# PART_2.net
KiCad netlist of a schematic drawn in Altium Designer
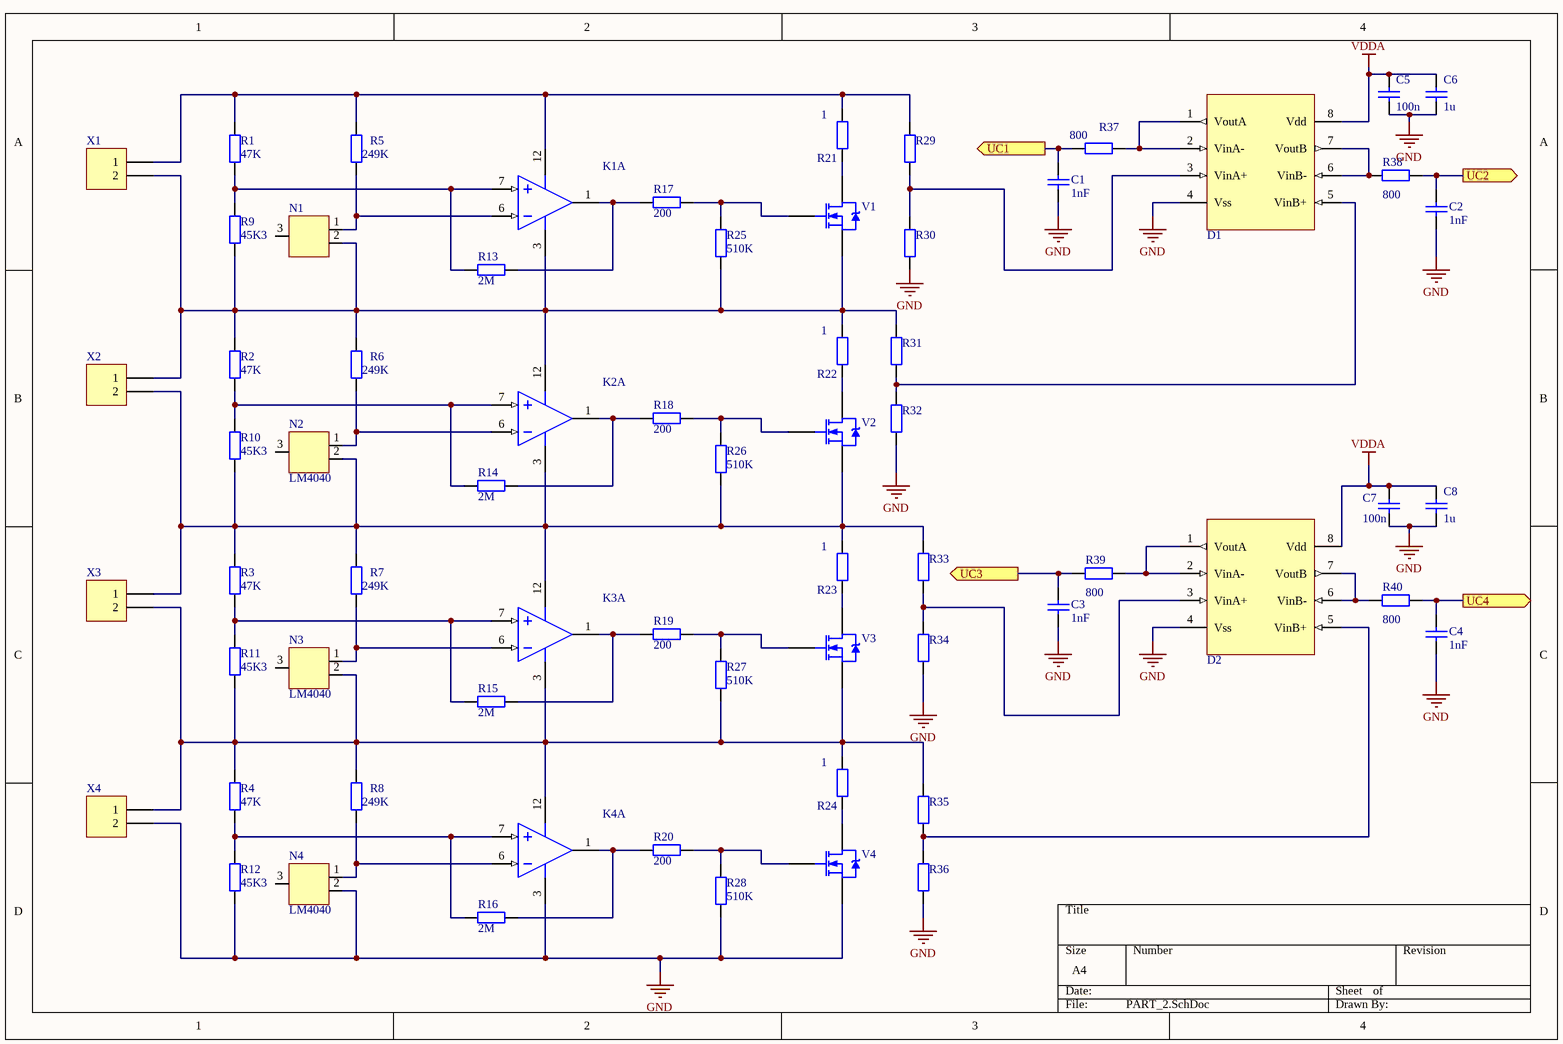
[diagram p0: PART_2.SchDoc]

(export (version "E")
  (design (tool "Eeschema 10.0.6"))
  (components
    (comp (ref "C1")
      (value "1nF")
      (footprint "C0805")
      (description "Capacitor")
      (fields (field (name "Comment") "Cap"))
      (libsource (lib "Miscellaneous Devices") (part "Cap"))
    )
    (comp (ref "C2")
      (value "1nF")
      (footprint "C0805")
      (description "Capacitor")
      (fields (field (name "Comment") "Cap"))
      (libsource (lib "Miscellaneous Devices") (part "Cap"))
    )
    (comp (ref "C3")
      (value "1nF")
      (footprint "C0805")
      (description "Capacitor")
      (fields (field (name "Comment") "Cap"))
      (libsource (lib "Miscellaneous Devices") (part "Cap"))
    )
    (comp (ref "C4")
      (value "1nF")
      (footprint "C0805")
      (description "Capacitor")
      (fields (field (name "Comment") "Cap"))
      (libsource (lib "Miscellaneous Devices") (part "Cap"))
    )
    (comp (ref "C5")
      (value "100n")
      (footprint "C0805")
      (description "Capacitor")
      (libsource (lib "Miscellaneous Devices") (part "Cap"))
    )
    (comp (ref "C6")
      (value "1u")
      (footprint "C0805")
      (description "Capacitor")
      (libsource (lib "Miscellaneous Devices") (part "Cap"))
    )
    (comp (ref "C7")
      (value "100n")
      (footprint "C0805")
      (description "Capacitor")
      (libsource (lib "Miscellaneous Devices") (part "Cap"))
    )
    (comp (ref "C8")
      (value "1u")
      (footprint "C0805")
      (description "Capacitor")
      (libsource (lib "Miscellaneous Devices") (part "Cap"))
    )
    (comp (ref "D1")
      (value "~")
      (footprint "MSOP za MCP6242")
      (libsource (lib "komponente") (part "Amplifier"))
    )
    (comp (ref "D2")
      (value "~")
      (footprint "MSOP za MCP6242")
      (libsource (lib "komponente") (part "Amplifier"))
    )
    (comp (ref "K1")
      (value "TLC3704QJ")
      (footprint "TSSOP5-3")
      (description "Low Power Quad Differential Comparator")
      (libsource (lib "TI Analog Comparator") (part "LP2901D"))
    )
    (comp (ref "K2")
      (value "TLC3704QJ")
      (footprint "TSSOP5-3")
      (description "Low Power Quad Differential Comparator")
      (libsource (lib "TI Analog Comparator") (part "LP2901D"))
    )
    (comp (ref "K3")
      (value "TLC3704QJ")
      (footprint "TSSOP5-3")
      (description "Low Power Quad Differential Comparator")
      (libsource (lib "TI Analog Comparator") (part "LP2901D"))
    )
    (comp (ref "K4")
      (value "TLC3704QJ")
      (footprint "TSSOP5-3")
      (description "Low Power Quad Differential Comparator")
      (libsource (lib "TI Analog Comparator") (part "LP2901D"))
    )
    (comp (ref "N1")
      (value "~")
      (footprint "SOT-23-ref_chip")
      (libsource (lib "komponente") (part "referentni chip"))
    )
    (comp (ref "N2")
      (value "LM4040")
      (footprint "SOT-23-ref_chip")
      (libsource (lib "komponente") (part "referentni chip"))
    )
    (comp (ref "N3")
      (value "LM4040")
      (footprint "SOT-23-ref_chip")
      (libsource (lib "komponente") (part "referentni chip"))
    )
    (comp (ref "N4")
      (value "LM4040")
      (footprint "SOT-23-ref_chip")
      (libsource (lib "komponente") (part "referentni chip"))
    )
    (comp (ref "R1")
      (value "47K")
      (footprint "C0805")
      (description "Resistor")
      (libsource (lib "Miscellaneous Devices") (part "Res2"))
    )
    (comp (ref "R2")
      (value "47K")
      (footprint "C0805")
      (description "Resistor")
      (libsource (lib "Miscellaneous Devices") (part "Res2"))
    )
    (comp (ref "R3")
      (value "47K")
      (footprint "C0805")
      (description "Resistor")
      (libsource (lib "Miscellaneous Devices") (part "Res2"))
    )
    (comp (ref "R4")
      (value "47K")
      (footprint "C0805")
      (description "Resistor")
      (libsource (lib "Miscellaneous Devices") (part "Res2"))
    )
    (comp (ref "R5")
      (value "249K")
      (footprint "C0805")
      (description "Resistor")
      (libsource (lib "Miscellaneous Devices") (part "Res2"))
    )
    (comp (ref "R6")
      (value "249K")
      (footprint "C0805")
      (description "Resistor")
      (libsource (lib "Miscellaneous Devices") (part "Res2"))
    )
    (comp (ref "R7")
      (value "249K")
      (footprint "C0805")
      (description "Resistor")
      (libsource (lib "Miscellaneous Devices") (part "Res2"))
    )
    (comp (ref "R8")
      (value "249K")
      (footprint "C0805")
      (description "Resistor")
      (libsource (lib "Miscellaneous Devices") (part "Res2"))
    )
    (comp (ref "R9")
      (value "45K3")
      (footprint "C0805")
      (description "Resistor")
      (libsource (lib "Miscellaneous Devices") (part "Res2"))
    )
    (comp (ref "R10")
      (value "45K3")
      (footprint "C0805")
      (description "Resistor")
      (libsource (lib "Miscellaneous Devices") (part "Res2"))
    )
    (comp (ref "R11")
      (value "45K3")
      (footprint "C0805")
      (description "Resistor")
      (libsource (lib "Miscellaneous Devices") (part "Res2"))
    )
    (comp (ref "R12")
      (value "45K3")
      (footprint "C0805")
      (description "Resistor")
      (libsource (lib "Miscellaneous Devices") (part "Res2"))
    )
    (comp (ref "R13")
      (value "2M")
      (footprint "C0805")
      (description "Resistor")
      (libsource (lib "") (part "Res2_1"))
    )
    (comp (ref "R14")
      (value "2M")
      (footprint "C0805")
      (description "Resistor")
      (libsource (lib "") (part "Res2_1"))
    )
    (comp (ref "R15")
      (value "2M")
      (footprint "C0805")
      (description "Resistor")
      (libsource (lib "") (part "Res2_1"))
    )
    (comp (ref "R16")
      (value "2M")
      (footprint "C0805")
      (description "Resistor")
      (libsource (lib "") (part "Res2_1"))
    )
    (comp (ref "R17")
      (value "200")
      (footprint "C0805")
      (description "Resistor")
      (libsource (lib "") (part "Res2_1"))
    )
    (comp (ref "R18")
      (value "200")
      (footprint "C0805")
      (description "Resistor")
      (libsource (lib "") (part "Res2_1"))
    )
    (comp (ref "R19")
      (value "200")
      (footprint "C0805")
      (description "Resistor")
      (libsource (lib "") (part "Res2_1"))
    )
    (comp (ref "R20")
      (value "200")
      (footprint "C0805")
      (description "Resistor")
      (libsource (lib "") (part "Res2_1"))
    )
    (comp (ref "R21")
      (value "1")
      (footprint "F za 7W otpornik")
      (description "Resistor")
      (libsource (lib "Miscellaneous Devices") (part "Res2"))
    )
    (comp (ref "R22")
      (value "1")
      (footprint "F za 7W otpornik")
      (description "Resistor")
      (libsource (lib "Miscellaneous Devices") (part "Res2"))
    )
    (comp (ref "R23")
      (value "1")
      (footprint "F za 7W otpornik")
      (description "Resistor")
      (libsource (lib "Miscellaneous Devices") (part "Res2"))
    )
    (comp (ref "R24")
      (value "1")
      (footprint "F za 7W otpornik")
      (description "Resistor")
      (libsource (lib "Miscellaneous Devices") (part "Res2"))
    )
    (comp (ref "R25")
      (value "510K")
      (footprint "C0805")
      (description "Resistor")
      (libsource (lib "Miscellaneous Devices") (part "Res2"))
    )
    (comp (ref "R26")
      (value "510K")
      (footprint "C0805")
      (description "Resistor")
      (libsource (lib "Miscellaneous Devices") (part "Res2"))
    )
    (comp (ref "R27")
      (value "510K")
      (footprint "C0805")
      (description "Resistor")
      (libsource (lib "Miscellaneous Devices") (part "Res2"))
    )
    (comp (ref "R28")
      (value "510K")
      (footprint "C0805")
      (description "Resistor")
      (libsource (lib "Miscellaneous Devices") (part "Res2"))
    )
    (comp (ref "R29")
      (value "~")
      (footprint "C0805")
      (description "Resistor")
      (libsource (lib "Miscellaneous Devices") (part "Res2"))
    )
    (comp (ref "R30")
      (value "~")
      (footprint "C0805")
      (description "Resistor")
      (libsource (lib "Miscellaneous Devices") (part "Res2"))
    )
    (comp (ref "R31")
      (value "~")
      (footprint "C0805")
      (description "Resistor")
      (libsource (lib "Miscellaneous Devices") (part "Res2"))
    )
    (comp (ref "R32")
      (value "~")
      (footprint "C0805")
      (description "Resistor")
      (libsource (lib "Miscellaneous Devices") (part "Res2"))
    )
    (comp (ref "R33")
      (value "~")
      (footprint "C0805")
      (description "Resistor")
      (libsource (lib "Miscellaneous Devices") (part "Res2"))
    )
    (comp (ref "R34")
      (value "~")
      (footprint "C0805")
      (description "Resistor")
      (libsource (lib "Miscellaneous Devices") (part "Res2"))
    )
    (comp (ref "R35")
      (value "~")
      (footprint "C0805")
      (description "Resistor")
      (libsource (lib "Miscellaneous Devices") (part "Res2"))
    )
    (comp (ref "R36")
      (value "~")
      (footprint "C0805")
      (description "Resistor")
      (libsource (lib "Miscellaneous Devices") (part "Res2"))
    )
    (comp (ref "R37")
      (value "800")
      (footprint "C0805")
      (description "Resistor")
      (libsource (lib "") (part "Res2_1"))
    )
    (comp (ref "R38")
      (value "800")
      (footprint "C0805")
      (description "Resistor")
      (libsource (lib "") (part "Res2_2"))
    )
    (comp (ref "R39")
      (value "800")
      (footprint "C0805")
      (description "Resistor")
      (libsource (lib "") (part "Res2_2"))
    )
    (comp (ref "R40")
      (value "800")
      (footprint "C0805")
      (description "Resistor")
      (libsource (lib "") (part "Res2_2"))
    )
    (comp (ref "V1")
      (value "NMOS-2")
      (footprint "SO-8L single_f")
      (description "N-Channel Power MOSFET")
      (libsource (lib "Miscellaneous Devices") (part "NMOS-2"))
    )
    (comp (ref "V2")
      (value "NMOS-2")
      (footprint "SO-8L single_f")
      (description "N-Channel Power MOSFET")
      (libsource (lib "Miscellaneous Devices") (part "NMOS-2"))
    )
    (comp (ref "V3")
      (value "NMOS-2")
      (footprint "SO-8L single_f")
      (description "N-Channel Power MOSFET")
      (libsource (lib "Miscellaneous Devices") (part "NMOS-2"))
    )
    (comp (ref "V4")
      (value "NMOS-2")
      (footprint "SO-8L single_f")
      (description "N-Channel Power MOSFET")
      (libsource (lib "Miscellaneous Devices") (part "NMOS-2"))
    )
    (comp (ref "X1")
      (value "Header 2")
      (footprint "F Header 1x2")
      (description "Header, 2-Pin")
      (libsource (lib "Miscellaneous Connectors") (part "Header 2"))
    )
    (comp (ref "X2")
      (value "Header 2")
      (footprint "F Header 1x2")
      (description "Header, 2-Pin")
      (libsource (lib "Miscellaneous Connectors") (part "Header 2"))
    )
    (comp (ref "X3")
      (value "Header 2")
      (footprint "F Header 1x2")
      (description "Header, 2-Pin")
      (libsource (lib "Miscellaneous Connectors") (part "Header 2"))
    )
    (comp (ref "X4")
      (value "Header 2")
      (footprint "F Header 1x2")
      (description "Header, 2-Pin")
      (libsource (lib "Miscellaneous Connectors") (part "Header 2"))
    )
  )
  (nets
    (net (code "1") (name "/UC1") (class "Default")
      (node (ref "C1") (pin "2") (pinfunction "2_2") (pintype "passive"))
      (node (ref "R37") (pin "2") (pinfunction "2_2") (pintype "passive"))
    )
    (net (code "2") (name "/UC2") (class "Default")
      (node (ref "C2") (pin "2") (pinfunction "2_2") (pintype "passive"))
      (node (ref "R38") (pin "2") (pinfunction "2_2") (pintype "passive"))
    )
    (net (code "3") (name "/UC3") (class "Default")
      (node (ref "C3") (pin "2") (pinfunction "2_2") (pintype "passive"))
      (node (ref "R39") (pin "1") (pinfunction "1_1") (pintype "passive"))
    )
    (net (code "4") (name "/UC4") (class "Default")
      (node (ref "C4") (pin "2") (pinfunction "2_2") (pintype "passive"))
      (node (ref "R40") (pin "2") (pinfunction "2_2") (pintype "passive"))
    )
    (net (code "5") (name "GND") (class "Default")
      (node (ref "C1") (pin "1") (pinfunction "1_1") (pintype "passive"))
      (node (ref "C2") (pin "1") (pinfunction "1_1") (pintype "passive"))
      (node (ref "C3") (pin "1") (pinfunction "1_1") (pintype "passive"))
      (node (ref "C4") (pin "1") (pinfunction "1_1") (pintype "passive"))
      (node (ref "C5") (pin "2") (pinfunction "2_2") (pintype "passive"))
      (node (ref "C6") (pin "2") (pinfunction "2_2") (pintype "passive"))
      (node (ref "C7") (pin "2") (pinfunction "2_2") (pintype "passive"))
      (node (ref "C8") (pin "2") (pinfunction "2_2") (pintype "passive"))
      (node (ref "D1") (pin "4") (pinfunction "Vss_4") (pintype "power_in"))
      (node (ref "D2") (pin "4") (pinfunction "Vss_4") (pintype "power_in"))
      (node (ref "K4") (pin "3") (pinfunction "V+_3") (pintype "passive"))
      (node (ref "N4") (pin "2") (pinfunction "2_2") (pintype "passive"))
      (node (ref "R12") (pin "1") (pinfunction "1_1") (pintype "passive"))
      (node (ref "R28") (pin "1") (pinfunction "1_1") (pintype "passive"))
      (node (ref "R30") (pin "1") (pinfunction "1_1") (pintype "passive"))
      (node (ref "R32") (pin "1") (pinfunction "1_1") (pintype "passive"))
      (node (ref "R34") (pin "1") (pinfunction "1_1") (pintype "passive"))
      (node (ref "R36") (pin "1") (pinfunction "1_1") (pintype "passive"))
      (node (ref "V4") (pin "3") (pinfunction "S_3") (pintype "passive"))
      (node (ref "X4") (pin "2") (pinfunction "2_2") (pintype "passive"))
    )
    (net (code "6") (name "Net-(D1-VinA+)") (class "Default")
      (node (ref "D1") (pin "3") (pinfunction "VinA+_3") (pintype "input"))
      (node (ref "R29") (pin "1") (pinfunction "1_1") (pintype "passive"))
      (node (ref "R30") (pin "2") (pinfunction "2_2") (pintype "passive"))
    )
    (net (code "7") (name "Net-(D1-VinA-)") (class "Default")
      (node (ref "D1") (pin "1") (pinfunction "VoutA_1") (pintype "output"))
      (node (ref "D1") (pin "2") (pinfunction "VinA-_2") (pintype "input"))
      (node (ref "R37") (pin "1") (pinfunction "1_1") (pintype "passive"))
    )
    (net (code "8") (name "Net-(D1-VinB+)") (class "Default")
      (node (ref "D1") (pin "5") (pinfunction "VinB+_5") (pintype "input"))
      (node (ref "R31") (pin "1") (pinfunction "1_1") (pintype "passive"))
      (node (ref "R32") (pin "2") (pinfunction "2_2") (pintype "passive"))
    )
    (net (code "9") (name "Net-(D1-VinB-)") (class "Default")
      (node (ref "D1") (pin "6") (pinfunction "VinB-_6") (pintype "input"))
      (node (ref "D1") (pin "7") (pinfunction "VoutB_7") (pintype "output"))
      (node (ref "R38") (pin "1") (pinfunction "1_1") (pintype "passive"))
    )
    (net (code "10") (name "Net-(D2-VinA+)") (class "Default")
      (node (ref "D2") (pin "3") (pinfunction "VinA+_3") (pintype "input"))
      (node (ref "R33") (pin "1") (pinfunction "1_1") (pintype "passive"))
      (node (ref "R34") (pin "2") (pinfunction "2_2") (pintype "passive"))
    )
    (net (code "11") (name "Net-(D2-VinA-)") (class "Default")
      (node (ref "D2") (pin "1") (pinfunction "VoutA_1") (pintype "output"))
      (node (ref "D2") (pin "2") (pinfunction "VinA-_2") (pintype "input"))
      (node (ref "R39") (pin "2") (pinfunction "2_2") (pintype "passive"))
    )
    (net (code "12") (name "Net-(D2-VinB+)") (class "Default")
      (node (ref "D2") (pin "5") (pinfunction "VinB+_5") (pintype "input"))
      (node (ref "R35") (pin "1") (pinfunction "1_1") (pintype "passive"))
      (node (ref "R36") (pin "2") (pinfunction "2_2") (pintype "passive"))
    )
    (net (code "13") (name "Net-(D2-VinB-)") (class "Default")
      (node (ref "D2") (pin "6") (pinfunction "VinB-_6") (pintype "input"))
      (node (ref "D2") (pin "7") (pinfunction "VoutB_7") (pintype "output"))
      (node (ref "R40") (pin "1") (pinfunction "1_1") (pintype "passive"))
    )
    (net (code "14") (name "Net-(K1A-IN+)") (class "Default")
      (node (ref "K1") (pin "7") (pinfunction "IN+_7") (pintype "input"))
      (node (ref "R1") (pin "1") (pinfunction "1_1") (pintype "passive"))
      (node (ref "R13") (pin "2") (pinfunction "2_2") (pintype "passive"))
      (node (ref "R9") (pin "2") (pinfunction "2_2") (pintype "passive"))
    )
    (net (code "15") (name "Net-(K1A-IN-)") (class "Default")
      (node (ref "K1") (pin "6") (pinfunction "IN-_6") (pintype "input"))
      (node (ref "N1") (pin "1") (pinfunction "1_1") (pintype "bidirectional"))
      (node (ref "R5") (pin "1") (pinfunction "1_1") (pintype "passive"))
    )
    (net (code "16") (name "Net-(K1A-OUT)") (class "Default")
      (node (ref "K1") (pin "1") (pinfunction "OUT_1") (pintype "open_collector"))
      (node (ref "R13") (pin "1") (pinfunction "1_1") (pintype "passive"))
      (node (ref "R17") (pin "2") (pinfunction "2_2") (pintype "passive"))
    )
    (net (code "17") (name "Net-(K1A-V+)") (class "Default")
      (node (ref "K1") (pin "3") (pinfunction "V+_3") (pintype "passive"))
      (node (ref "K2") (pin "12") (pinfunction "V-_12") (pintype "passive"))
      (node (ref "N1") (pin "2") (pinfunction "2_2") (pintype "passive"))
      (node (ref "R2") (pin "2") (pinfunction "2_2") (pintype "passive"))
      (node (ref "R22") (pin "2") (pinfunction "2_2") (pintype "passive"))
      (node (ref "R25") (pin "1") (pinfunction "1_1") (pintype "passive"))
      (node (ref "R31") (pin "2") (pinfunction "2_2") (pintype "passive"))
      (node (ref "R6") (pin "2") (pinfunction "2_2") (pintype "passive"))
      (node (ref "R9") (pin "1") (pinfunction "1_1") (pintype "passive"))
      (node (ref "V1") (pin "3") (pinfunction "S_3") (pintype "passive"))
      (node (ref "X1") (pin "2") (pinfunction "2_2") (pintype "passive"))
      (node (ref "X2") (pin "1") (pinfunction "1_1") (pintype "passive"))
    )
    (net (code "18") (name "Net-(K1A-V-)") (class "Default")
      (node (ref "K1") (pin "12") (pinfunction "V-_12") (pintype "passive"))
      (node (ref "R1") (pin "2") (pinfunction "2_2") (pintype "passive"))
      (node (ref "R21") (pin "2") (pinfunction "2_2") (pintype "passive"))
      (node (ref "R29") (pin "2") (pinfunction "2_2") (pintype "passive"))
      (node (ref "R5") (pin "2") (pinfunction "2_2") (pintype "passive"))
      (node (ref "X1") (pin "1") (pinfunction "1_1") (pintype "passive"))
    )
    (net (code "19") (name "Net-(K2A-IN+)") (class "Default")
      (node (ref "K2") (pin "7") (pinfunction "IN+_7") (pintype "input"))
      (node (ref "R10") (pin "2") (pinfunction "2_2") (pintype "passive"))
      (node (ref "R14") (pin "2") (pinfunction "2_2") (pintype "passive"))
      (node (ref "R2") (pin "1") (pinfunction "1_1") (pintype "passive"))
    )
    (net (code "20") (name "Net-(K2A-IN-)") (class "Default")
      (node (ref "K2") (pin "6") (pinfunction "IN-_6") (pintype "input"))
      (node (ref "N2") (pin "1") (pinfunction "1_1") (pintype "bidirectional"))
      (node (ref "R6") (pin "1") (pinfunction "1_1") (pintype "passive"))
    )
    (net (code "21") (name "Net-(K2A-OUT)") (class "Default")
      (node (ref "K2") (pin "1") (pinfunction "OUT_1") (pintype "open_collector"))
      (node (ref "R14") (pin "1") (pinfunction "1_1") (pintype "passive"))
      (node (ref "R18") (pin "2") (pinfunction "2_2") (pintype "passive"))
    )
    (net (code "22") (name "Net-(K2A-V+)") (class "Default")
      (node (ref "K2") (pin "3") (pinfunction "V+_3") (pintype "passive"))
      (node (ref "K3") (pin "12") (pinfunction "V-_12") (pintype "passive"))
      (node (ref "N2") (pin "2") (pinfunction "2_2") (pintype "passive"))
      (node (ref "R10") (pin "1") (pinfunction "1_1") (pintype "passive"))
      (node (ref "R23") (pin "2") (pinfunction "2_2") (pintype "passive"))
      (node (ref "R26") (pin "1") (pinfunction "1_1") (pintype "passive"))
      (node (ref "R3") (pin "2") (pinfunction "2_2") (pintype "passive"))
      (node (ref "R33") (pin "2") (pinfunction "2_2") (pintype "passive"))
      (node (ref "R7") (pin "2") (pinfunction "2_2") (pintype "passive"))
      (node (ref "V2") (pin "3") (pinfunction "S_3") (pintype "passive"))
      (node (ref "X2") (pin "2") (pinfunction "2_2") (pintype "passive"))
      (node (ref "X3") (pin "1") (pinfunction "1_1") (pintype "passive"))
    )
    (net (code "23") (name "Net-(K3A-IN+)") (class "Default")
      (node (ref "K3") (pin "7") (pinfunction "IN+_7") (pintype "input"))
      (node (ref "R11") (pin "2") (pinfunction "2_2") (pintype "passive"))
      (node (ref "R15") (pin "2") (pinfunction "2_2") (pintype "passive"))
      (node (ref "R3") (pin "1") (pinfunction "1_1") (pintype "passive"))
    )
    (net (code "24") (name "Net-(K3A-IN-)") (class "Default")
      (node (ref "K3") (pin "6") (pinfunction "IN-_6") (pintype "input"))
      (node (ref "N3") (pin "1") (pinfunction "1_1") (pintype "bidirectional"))
      (node (ref "R7") (pin "1") (pinfunction "1_1") (pintype "passive"))
    )
    (net (code "25") (name "Net-(K3A-OUT)") (class "Default")
      (node (ref "K3") (pin "1") (pinfunction "OUT_1") (pintype "open_collector"))
      (node (ref "R15") (pin "1") (pinfunction "1_1") (pintype "passive"))
      (node (ref "R19") (pin "2") (pinfunction "2_2") (pintype "passive"))
    )
    (net (code "26") (name "Net-(K3A-V+)") (class "Default")
      (node (ref "K3") (pin "3") (pinfunction "V+_3") (pintype "passive"))
      (node (ref "K4") (pin "12") (pinfunction "V-_12") (pintype "passive"))
      (node (ref "N3") (pin "2") (pinfunction "2_2") (pintype "passive"))
      (node (ref "R11") (pin "1") (pinfunction "1_1") (pintype "passive"))
      (node (ref "R24") (pin "2") (pinfunction "2_2") (pintype "passive"))
      (node (ref "R27") (pin "1") (pinfunction "1_1") (pintype "passive"))
      (node (ref "R35") (pin "2") (pinfunction "2_2") (pintype "passive"))
      (node (ref "R4") (pin "2") (pinfunction "2_2") (pintype "passive"))
      (node (ref "R8") (pin "2") (pinfunction "2_2") (pintype "passive"))
      (node (ref "V3") (pin "3") (pinfunction "S_3") (pintype "passive"))
      (node (ref "X3") (pin "2") (pinfunction "2_2") (pintype "passive"))
      (node (ref "X4") (pin "1") (pinfunction "1_1") (pintype "passive"))
    )
    (net (code "27") (name "Net-(K4A-IN+)") (class "Default")
      (node (ref "K4") (pin "7") (pinfunction "IN+_7") (pintype "input"))
      (node (ref "R12") (pin "2") (pinfunction "2_2") (pintype "passive"))
      (node (ref "R16") (pin "2") (pinfunction "2_2") (pintype "passive"))
      (node (ref "R4") (pin "1") (pinfunction "1_1") (pintype "passive"))
    )
    (net (code "28") (name "Net-(K4A-IN-)") (class "Default")
      (node (ref "K4") (pin "6") (pinfunction "IN-_6") (pintype "input"))
      (node (ref "N4") (pin "1") (pinfunction "1_1") (pintype "bidirectional"))
      (node (ref "R8") (pin "1") (pinfunction "1_1") (pintype "passive"))
    )
    (net (code "29") (name "Net-(K4A-OUT)") (class "Default")
      (node (ref "K4") (pin "1") (pinfunction "OUT_1") (pintype "open_collector"))
      (node (ref "R16") (pin "1") (pinfunction "1_1") (pintype "passive"))
      (node (ref "R20") (pin "2") (pinfunction "2_2") (pintype "passive"))
    )
    (net (code "30") (name "Net-(V1-D)") (class "Default")
      (node (ref "R21") (pin "1") (pinfunction "1_1") (pintype "passive"))
      (node (ref "V1") (pin "2") (pinfunction "D_2") (pintype "passive"))
    )
    (net (code "31") (name "Net-(V1-G)") (class "Default")
      (node (ref "R17") (pin "1") (pinfunction "1_1") (pintype "passive"))
      (node (ref "R25") (pin "2") (pinfunction "2_2") (pintype "passive"))
      (node (ref "V1") (pin "1") (pinfunction "G_1") (pintype "passive"))
    )
    (net (code "32") (name "Net-(V2-D)") (class "Default")
      (node (ref "R22") (pin "1") (pinfunction "1_1") (pintype "passive"))
      (node (ref "V2") (pin "2") (pinfunction "D_2") (pintype "passive"))
    )
    (net (code "33") (name "Net-(V2-G)") (class "Default")
      (node (ref "R18") (pin "1") (pinfunction "1_1") (pintype "passive"))
      (node (ref "R26") (pin "2") (pinfunction "2_2") (pintype "passive"))
      (node (ref "V2") (pin "1") (pinfunction "G_1") (pintype "passive"))
    )
    (net (code "34") (name "Net-(V3-D)") (class "Default")
      (node (ref "R23") (pin "1") (pinfunction "1_1") (pintype "passive"))
      (node (ref "V3") (pin "2") (pinfunction "D_2") (pintype "passive"))
    )
    (net (code "35") (name "Net-(V3-G)") (class "Default")
      (node (ref "R19") (pin "1") (pinfunction "1_1") (pintype "passive"))
      (node (ref "R27") (pin "2") (pinfunction "2_2") (pintype "passive"))
      (node (ref "V3") (pin "1") (pinfunction "G_1") (pintype "passive"))
    )
    (net (code "36") (name "Net-(V4-D)") (class "Default")
      (node (ref "R24") (pin "1") (pinfunction "1_1") (pintype "passive"))
      (node (ref "V4") (pin "2") (pinfunction "D_2") (pintype "passive"))
    )
    (net (code "37") (name "Net-(V4-G)") (class "Default")
      (node (ref "R20") (pin "1") (pinfunction "1_1") (pintype "passive"))
      (node (ref "R28") (pin "2") (pinfunction "2_2") (pintype "passive"))
      (node (ref "V4") (pin "1") (pinfunction "G_1") (pintype "passive"))
    )
    (net (code "38") (name "VDDA") (class "Default")
      (node (ref "C5") (pin "1") (pinfunction "1_1") (pintype "passive"))
      (node (ref "C6") (pin "1") (pinfunction "1_1") (pintype "passive"))
      (node (ref "C7") (pin "1") (pinfunction "1_1") (pintype "passive"))
      (node (ref "C8") (pin "1") (pinfunction "1_1") (pintype "passive"))
      (node (ref "D1") (pin "8") (pinfunction "Vdd_8") (pintype "power_in"))
      (node (ref "D2") (pin "8") (pinfunction "Vdd_8") (pintype "power_in"))
    )
    (net (code "39") (name "unconnected-(N1-Pad3)") (class "Default")
      (node (ref "N1") (pin "3") (pinfunction "3_3") (pintype "passive"))
    )
    (net (code "40") (name "unconnected-(N2-Pad3)") (class "Default")
      (node (ref "N2") (pin "3") (pinfunction "3_3") (pintype "passive"))
    )
    (net (code "41") (name "unconnected-(N3-Pad3)") (class "Default")
      (node (ref "N3") (pin "3") (pinfunction "3_3") (pintype "passive"))
    )
    (net (code "42") (name "unconnected-(N4-Pad3)") (class "Default")
      (node (ref "N4") (pin "3") (pinfunction "3_3") (pintype "passive"))
    )
    (net (code "43") (name "unconnected-(V1-S-Pad3)") (class "Default")
      (node (ref "V1") (pin "3") (pinfunction "S_3") (pintype "passive"))
    )
    (net (code "44") (name "unconnected-(V1-S-Pad3)_1") (class "Default")
      (node (ref "V1") (pin "3") (pinfunction "S_3") (pintype "passive"))
    )
    (net (code "45") (name "unconnected-(V2-S-Pad3)") (class "Default")
      (node (ref "V2") (pin "3") (pinfunction "S_3") (pintype "passive"))
    )
    (net (code "46") (name "unconnected-(V2-S-Pad3)_1") (class "Default")
      (node (ref "V2") (pin "3") (pinfunction "S_3") (pintype "passive"))
    )
    (net (code "47") (name "unconnected-(V3-S-Pad3)") (class "Default")
      (node (ref "V3") (pin "3") (pinfunction "S_3") (pintype "passive"))
    )
    (net (code "48") (name "unconnected-(V3-S-Pad3)_1") (class "Default")
      (node (ref "V3") (pin "3") (pinfunction "S_3") (pintype "passive"))
    )
    (net (code "49") (name "unconnected-(V4-S-Pad3)") (class "Default")
      (node (ref "V4") (pin "3") (pinfunction "S_3") (pintype "passive"))
    )
    (net (code "50") (name "unconnected-(V4-S-Pad3)_1") (class "Default")
      (node (ref "V4") (pin "3") (pinfunction "S_3") (pintype "passive"))
    )
  )
)
